# giraffe20_flipped.net
KiCad netlist of a schematic drawn in EAGLE
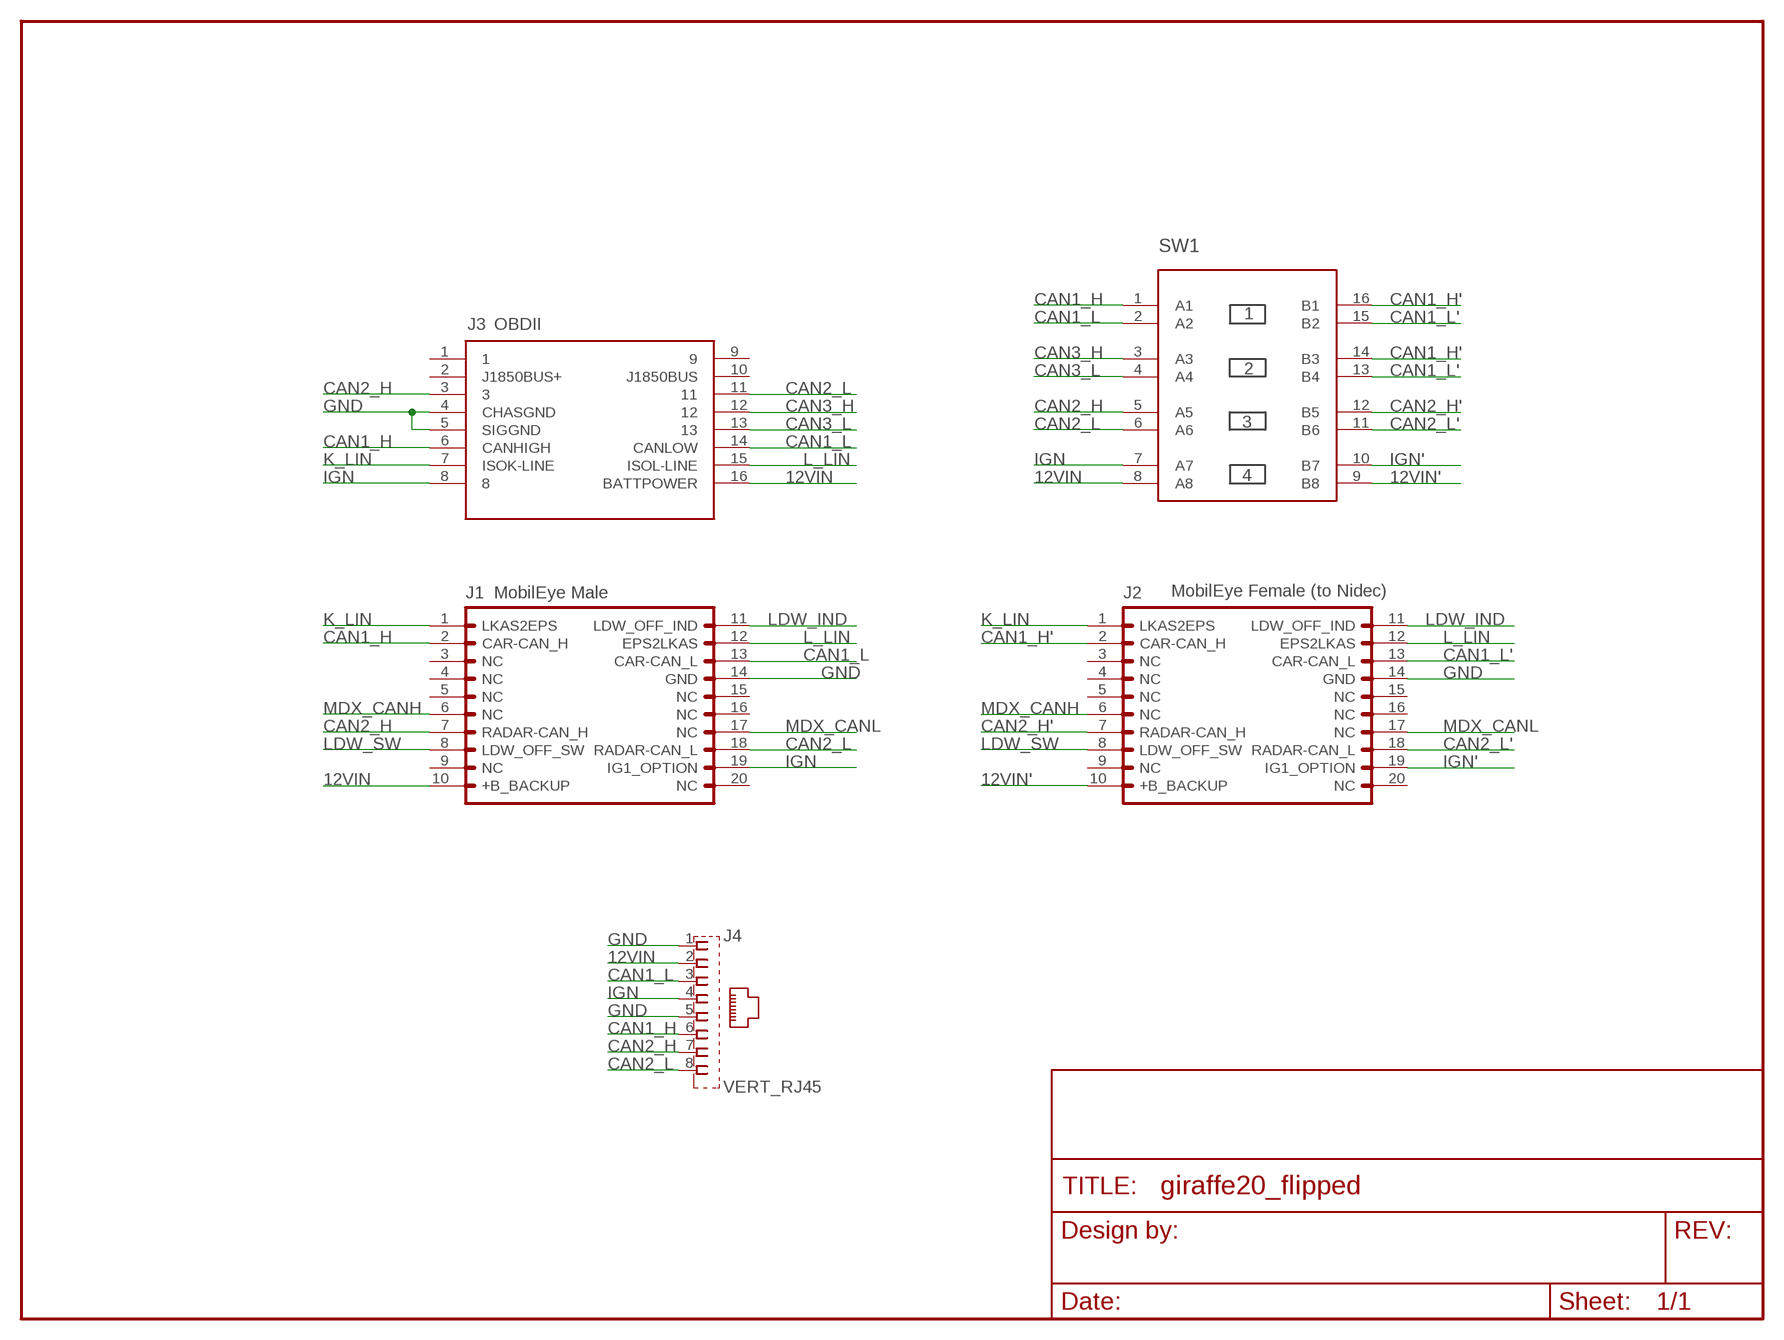
[diagram p0: schematic, sheet 1]

(export (version "E")
  (design (tool "Eeschema 10.0.6"))
  (components
    (comp (ref "FRAME1")
      (value "FRAME-LETTERNO_PACKAGE")
      (footprint "eagle-import:DUMMY")
      (fields (field (name "DESIGNER") "Nobody"))
      (libsource (lib "eagle-import") (part "FRAME-LETTERNO_PACKAGE"))
    )
    (comp (ref "J1")
      (value "MOBILEYERAMALE")
      (footprint "eagle-import:2X10(RA)")
      (libsource (lib "eagle-import") (part "MOBILEYERAMALE"))
    )
    (comp (ref "J2")
      (value "MOBILEYEFEMALE")
      (footprint "eagle-import:2X10(JAE_FEMALE)")
      (libsource (lib "eagle-import") (part "MOBILEYEFEMALE"))
    )
    (comp (ref "J3")
      (value "OBDII-FEMALE-CUT")
      (footprint "eagle-import:OBDII-FEMALE-MIDCUT")
      (libsource (lib "eagle-import") (part "OBDII-FEMALE-CUT"))
    )
    (comp (ref "J4")
      (value "VERT_RJ45")
      (footprint "eagle-import:GLX-S-88M")
      (libsource (lib "eagle-import") (part "VERT_RJ45"))
    )
    (comp (ref "SW1")
      (value "4XDPSTSMT")
      (footprint "eagle-import:4-DPST")
      (libsource (lib "eagle-import") (part "4XDPSTSMT"))
    )
  )
  (nets
    (net (code "1") (name "/12VIN") (class "Default")
      (node (ref "J1") (pin "10") (pinfunction "+B_BACKUP_10") (pintype "bidirectional"))
      (node (ref "J3") (pin "16") (pinfunction "BATTPOWER_16") (pintype "bidirectional"))
      (node (ref "J4") (pin "2") (pinfunction "2_2") (pintype "passive"))
      (node (ref "SW1") (pin "8") (pinfunction "A8_8") (pintype "bidirectional"))
    )
    (net (code "2") (name "/12VIN'") (class "Default")
      (node (ref "J2") (pin "10") (pinfunction "+B_BACKUP_10") (pintype "bidirectional"))
      (node (ref "SW1") (pin "9") (pinfunction "B8_9") (pintype "bidirectional"))
    )
    (net (code "3") (name "/CAN1_H") (class "Default")
      (node (ref "J1") (pin "2") (pinfunction "CAR-CAN_H_2") (pintype "bidirectional"))
      (node (ref "J3") (pin "6") (pinfunction "CANHIGH_6") (pintype "bidirectional"))
      (node (ref "J4") (pin "6") (pinfunction "6_6") (pintype "passive"))
      (node (ref "SW1") (pin "1") (pinfunction "A1_1") (pintype "bidirectional"))
    )
    (net (code "4") (name "/CAN1_H'") (class "Default")
      (node (ref "J2") (pin "2") (pinfunction "CAR-CAN_H_2") (pintype "bidirectional"))
      (node (ref "SW1") (pin "14") (pinfunction "B3_14") (pintype "bidirectional"))
      (node (ref "SW1") (pin "16") (pinfunction "B1_16") (pintype "bidirectional"))
    )
    (net (code "5") (name "/CAN1_L") (class "Default")
      (node (ref "J1") (pin "13") (pinfunction "CAR-CAN_L_13") (pintype "bidirectional"))
      (node (ref "J3") (pin "14") (pinfunction "CANLOW_14") (pintype "bidirectional"))
      (node (ref "J4") (pin "3") (pinfunction "3_3") (pintype "passive"))
      (node (ref "SW1") (pin "2") (pinfunction "A2_2") (pintype "bidirectional"))
    )
    (net (code "6") (name "/CAN1_L'") (class "Default")
      (node (ref "J2") (pin "13") (pinfunction "CAR-CAN_L_13") (pintype "bidirectional"))
      (node (ref "SW1") (pin "13") (pinfunction "B4_13") (pintype "bidirectional"))
      (node (ref "SW1") (pin "15") (pinfunction "B2_15") (pintype "bidirectional"))
    )
    (net (code "7") (name "/CAN2_H") (class "Default")
      (node (ref "J1") (pin "7") (pinfunction "RADAR-CAN_H_7") (pintype "bidirectional"))
      (node (ref "J3") (pin "3") (pinfunction "3_3") (pintype "bidirectional"))
      (node (ref "J4") (pin "7") (pinfunction "7_7") (pintype "passive"))
      (node (ref "SW1") (pin "5") (pinfunction "A5_5") (pintype "bidirectional"))
    )
    (net (code "8") (name "/CAN2_H'") (class "Default")
      (node (ref "J2") (pin "7") (pinfunction "RADAR-CAN_H_7") (pintype "bidirectional"))
      (node (ref "SW1") (pin "12") (pinfunction "B5_12") (pintype "bidirectional"))
    )
    (net (code "9") (name "/CAN2_L") (class "Default")
      (node (ref "J1") (pin "18") (pinfunction "RADAR-CAN_L_18") (pintype "bidirectional"))
      (node (ref "J3") (pin "11") (pinfunction "11_11") (pintype "bidirectional"))
      (node (ref "J4") (pin "8") (pinfunction "8_8") (pintype "passive"))
      (node (ref "SW1") (pin "6") (pinfunction "A6_6") (pintype "bidirectional"))
    )
    (net (code "10") (name "/CAN2_L'") (class "Default")
      (node (ref "J2") (pin "18") (pinfunction "RADAR-CAN_L_18") (pintype "bidirectional"))
      (node (ref "SW1") (pin "11") (pinfunction "B6_11") (pintype "bidirectional"))
    )
    (net (code "11") (name "/CAN3_H") (class "Default")
      (node (ref "J3") (pin "12") (pinfunction "12_12") (pintype "bidirectional"))
      (node (ref "SW1") (pin "3") (pinfunction "A3_3") (pintype "bidirectional"))
    )
    (net (code "12") (name "/CAN3_L") (class "Default")
      (node (ref "J3") (pin "13") (pinfunction "13_13") (pintype "bidirectional"))
      (node (ref "SW1") (pin "4") (pinfunction "A4_4") (pintype "bidirectional"))
    )
    (net (code "13") (name "/GND") (class "Default")
      (node (ref "J1") (pin "14") (pinfunction "GND_14") (pintype "bidirectional"))
      (node (ref "J2") (pin "14") (pinfunction "GND_14") (pintype "bidirectional"))
      (node (ref "J3") (pin "4") (pinfunction "CHASGND_4") (pintype "bidirectional"))
      (node (ref "J3") (pin "5") (pinfunction "SIGGND_5") (pintype "bidirectional"))
      (node (ref "J4") (pin "1") (pinfunction "1_1") (pintype "passive"))
      (node (ref "J4") (pin "5") (pinfunction "5_5") (pintype "passive"))
    )
    (net (code "14") (name "/IGN") (class "Default")
      (node (ref "J1") (pin "19") (pinfunction "IG1_OPTION_19") (pintype "bidirectional"))
      (node (ref "J3") (pin "8") (pinfunction "8_8") (pintype "bidirectional"))
      (node (ref "J4") (pin "4") (pinfunction "4_4") (pintype "passive"))
      (node (ref "SW1") (pin "7") (pinfunction "A7_7") (pintype "bidirectional"))
    )
    (net (code "15") (name "/IGN'") (class "Default")
      (node (ref "J2") (pin "19") (pinfunction "IG1_OPTION_19") (pintype "bidirectional"))
      (node (ref "SW1") (pin "10") (pinfunction "B7_10") (pintype "bidirectional"))
    )
    (net (code "16") (name "/K_LIN") (class "Default")
      (node (ref "J1") (pin "1") (pinfunction "LKAS2EPS_1") (pintype "bidirectional"))
      (node (ref "J2") (pin "1") (pinfunction "LKAS2EPS_1") (pintype "bidirectional"))
      (node (ref "J3") (pin "7") (pinfunction "ISOK-LINE_7") (pintype "bidirectional"))
    )
    (net (code "17") (name "/LDW_IND") (class "Default")
      (node (ref "J1") (pin "11") (pinfunction "LDW_OFF_IND_11") (pintype "bidirectional"))
      (node (ref "J2") (pin "11") (pinfunction "LDW_OFF_IND_11") (pintype "bidirectional"))
    )
    (net (code "18") (name "/LDW_SW") (class "Default")
      (node (ref "J1") (pin "8") (pinfunction "LDW_OFF_SW_8") (pintype "bidirectional"))
      (node (ref "J2") (pin "8") (pinfunction "LDW_OFF_SW_8") (pintype "bidirectional"))
    )
    (net (code "19") (name "/L_LIN") (class "Default")
      (node (ref "J1") (pin "12") (pinfunction "EPS2LKAS_12") (pintype "bidirectional"))
      (node (ref "J2") (pin "12") (pinfunction "EPS2LKAS_12") (pintype "bidirectional"))
      (node (ref "J3") (pin "15") (pinfunction "ISOL-LINE_15") (pintype "bidirectional"))
    )
    (net (code "20") (name "/MDX_CANH") (class "Default")
      (node (ref "J1") (pin "6") (pinfunction "NC_6") (pintype "bidirectional"))
      (node (ref "J2") (pin "6") (pinfunction "NC_6") (pintype "bidirectional"))
    )
    (net (code "21") (name "/MDX_CANL") (class "Default")
      (node (ref "J1") (pin "17") (pinfunction "NC_17") (pintype "bidirectional"))
      (node (ref "J2") (pin "17") (pinfunction "NC_17") (pintype "bidirectional"))
    )
    (net (code "22") (name "unconnected-(J1-NC-Pad3)") (class "Default")
      (node (ref "J1") (pin "3") (pinfunction "NC_3") (pintype "bidirectional"))
    )
    (net (code "23") (name "unconnected-(J1-NC-Pad4)") (class "Default")
      (node (ref "J1") (pin "4") (pinfunction "NC_4") (pintype "bidirectional"))
    )
    (net (code "24") (name "unconnected-(J1-NC-Pad5)") (class "Default")
      (node (ref "J1") (pin "5") (pinfunction "NC_5") (pintype "bidirectional"))
    )
    (net (code "25") (name "unconnected-(J1-NC-Pad9)") (class "Default")
      (node (ref "J1") (pin "9") (pinfunction "NC_9") (pintype "bidirectional"))
    )
    (net (code "26") (name "unconnected-(J1-NC-Pad15)") (class "Default")
      (node (ref "J1") (pin "15") (pinfunction "NC_15") (pintype "bidirectional"))
    )
    (net (code "27") (name "unconnected-(J1-NC-Pad16)") (class "Default")
      (node (ref "J1") (pin "16") (pinfunction "NC_16") (pintype "bidirectional"))
    )
    (net (code "28") (name "unconnected-(J1-NC-Pad20)") (class "Default")
      (node (ref "J1") (pin "20") (pinfunction "NC_20") (pintype "bidirectional"))
    )
    (net (code "29") (name "unconnected-(J2-NC-Pad3)") (class "Default")
      (node (ref "J2") (pin "3") (pinfunction "NC_3") (pintype "bidirectional"))
    )
    (net (code "30") (name "unconnected-(J2-NC-Pad4)") (class "Default")
      (node (ref "J2") (pin "4") (pinfunction "NC_4") (pintype "bidirectional"))
    )
    (net (code "31") (name "unconnected-(J2-NC-Pad5)") (class "Default")
      (node (ref "J2") (pin "5") (pinfunction "NC_5") (pintype "bidirectional"))
    )
    (net (code "32") (name "unconnected-(J2-NC-Pad9)") (class "Default")
      (node (ref "J2") (pin "9") (pinfunction "NC_9") (pintype "bidirectional"))
    )
    (net (code "33") (name "unconnected-(J2-NC-Pad15)") (class "Default")
      (node (ref "J2") (pin "15") (pinfunction "NC_15") (pintype "bidirectional"))
    )
    (net (code "34") (name "unconnected-(J2-NC-Pad16)") (class "Default")
      (node (ref "J2") (pin "16") (pinfunction "NC_16") (pintype "bidirectional"))
    )
    (net (code "35") (name "unconnected-(J2-NC-Pad20)") (class "Default")
      (node (ref "J2") (pin "20") (pinfunction "NC_20") (pintype "bidirectional"))
    )
    (net (code "36") (name "unconnected-(J3-J1850BUS+-Pad2)") (class "Default")
      (node (ref "J3") (pin "2") (pinfunction "J1850BUS+_2") (pintype "bidirectional"))
    )
    (net (code "37") (name "unconnected-(J3-J1850BUS-Pad10)") (class "Default")
      (node (ref "J3") (pin "10") (pinfunction "J1850BUS_10") (pintype "bidirectional"))
    )
    (net (code "38") (name "unconnected-(J3-Pad1)") (class "Default")
      (node (ref "J3") (pin "1") (pinfunction "1_1") (pintype "bidirectional"))
    )
    (net (code "39") (name "unconnected-(J3-Pad9)") (class "Default")
      (node (ref "J3") (pin "9") (pinfunction "9_9") (pintype "bidirectional"))
    )
  )
)
